# BMS_BQ76PL455.net
KiCad netlist of a schematic drawn in Altium Designer
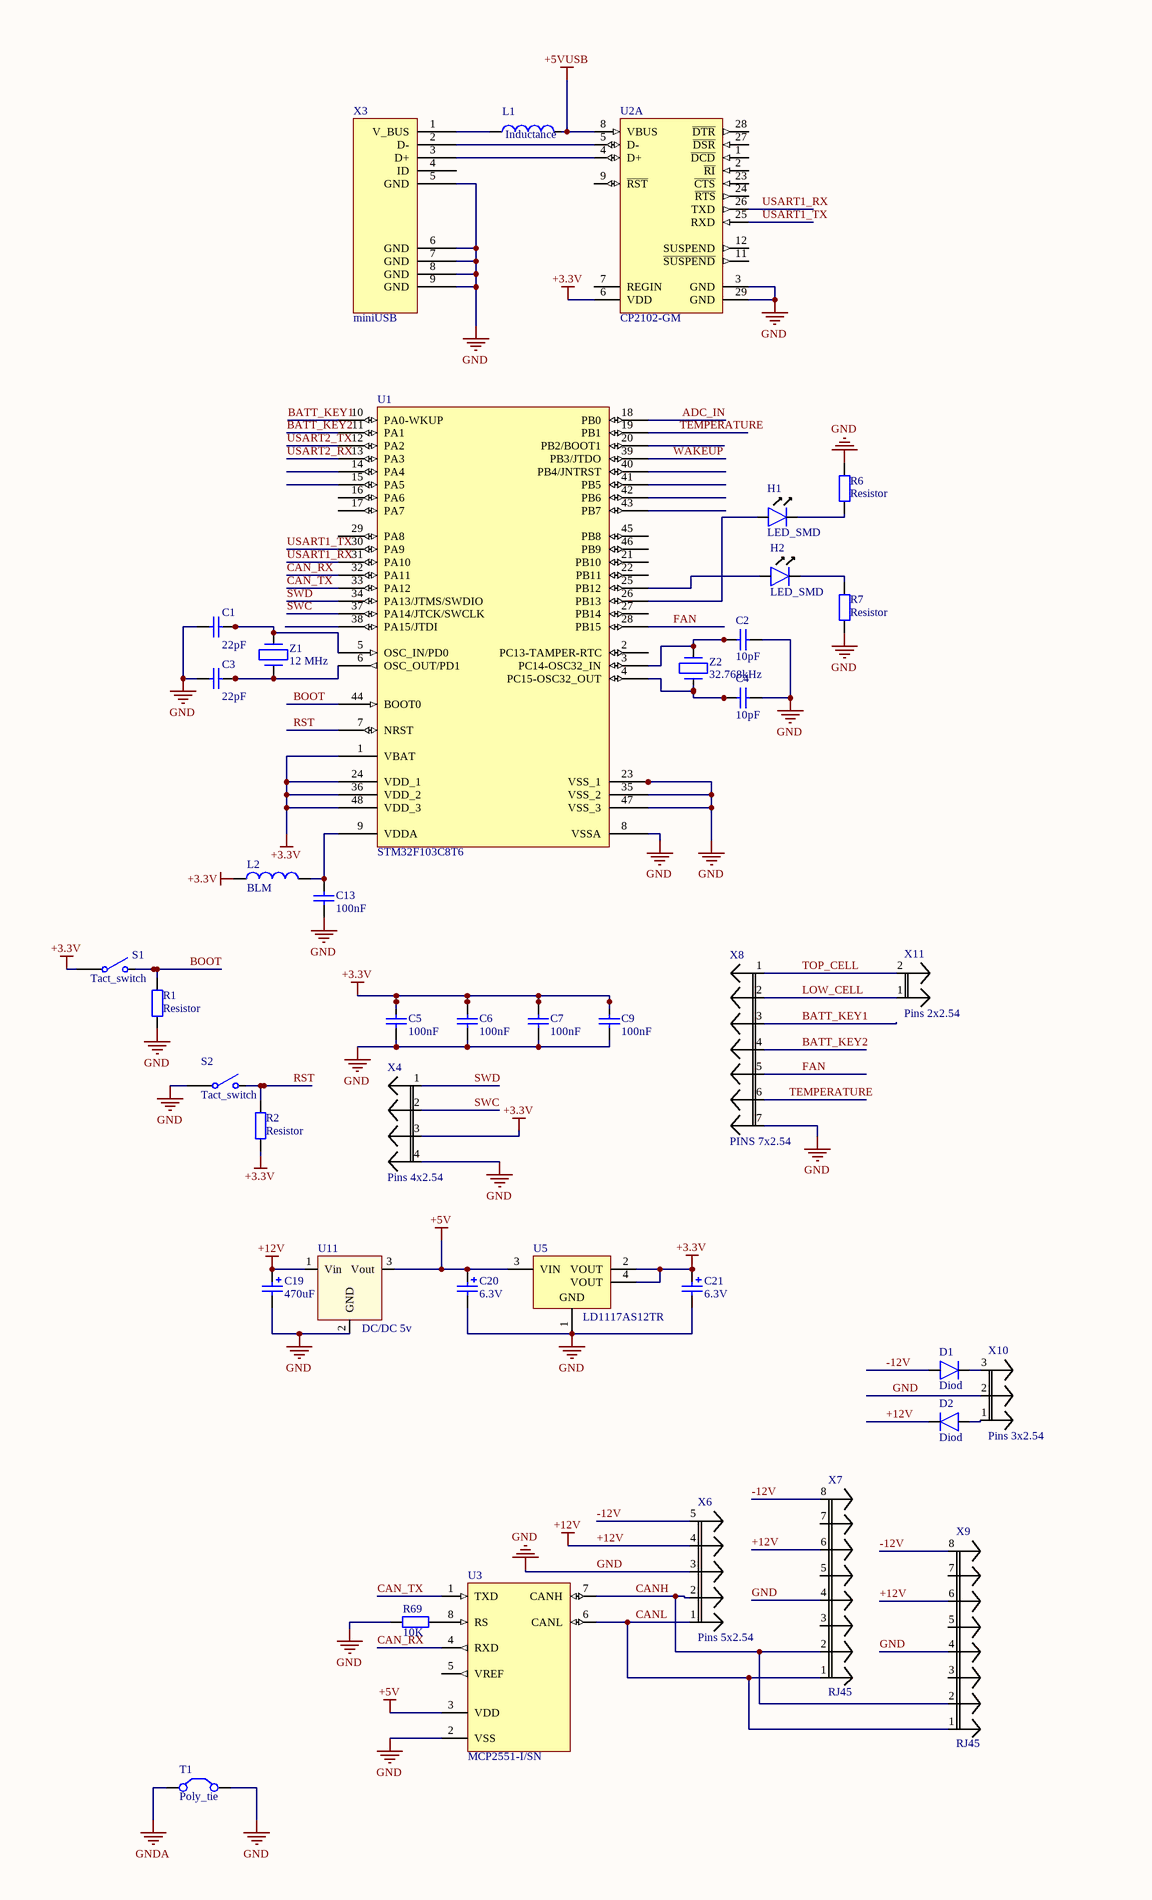
[diagram p0: BMS_BQ76PL455.SchDoc, left]
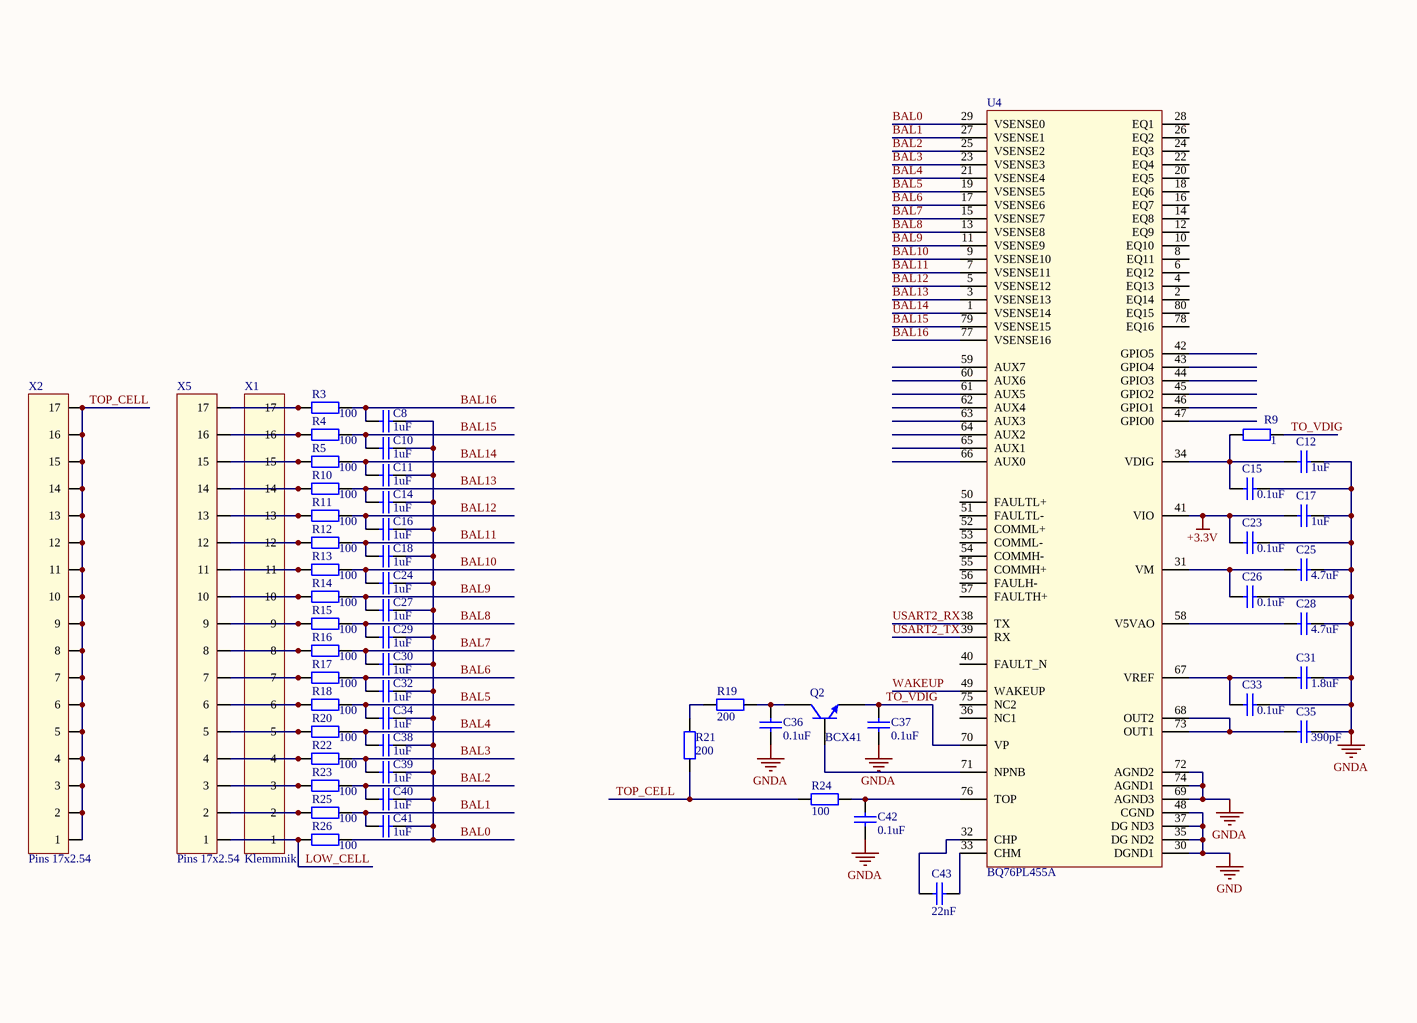
[diagram p1: BMS_BQ76PL455.SchDoc, right]

(export (version "E")
  (design (tool "Eeschema 10.0.6"))
  (components
    (comp (ref "C1") (value "22pF") (footprint "C0805") (libsource (lib "A_H_sch_lib") (part "Condensator")))
    (comp (ref "C2") (value "10pF") (footprint "C0805") (libsource (lib "A_H_sch_lib") (part "Condensator")))
    (comp (ref "C3") (value "22pF") (footprint "C0805") (libsource (lib "A_H_sch_lib") (part "Condensator")))
    (comp (ref "C4") (value "10pF") (footprint "C0805") (libsource (lib "A_H_sch_lib") (part "Condensator")))
    (comp (ref "C5") (value "100nF") (footprint "C0805") (libsource (lib "A_H_sch_lib") (part "Condensator")))
    (comp (ref "C6") (value "100nF") (footprint "C0805") (libsource (lib "A_H_sch_lib") (part "Condensator")))
    (comp (ref "C7") (value "100nF") (footprint "C0805") (libsource (lib "A_H_sch_lib") (part "Condensator")))
    (comp (ref "C8") (value "1uF") (footprint "C0805") (libsource (lib "A_H_sch_lib") (part "Condensator")))
    (comp (ref "C9") (value "100nF") (footprint "C0805") (libsource (lib "A_H_sch_lib") (part "Condensator")))
    (comp (ref "C10") (value "1uF") (footprint "C0805") (libsource (lib "A_H_sch_lib") (part "Condensator")))
    (comp (ref "C11") (value "1uF") (footprint "C0805") (libsource (lib "A_H_sch_lib") (part "Condensator")))
    (comp (ref "C12") (value "1uF") (footprint "C0805") (libsource (lib "A_H_sch_lib") (part "Condensator")))
    (comp (ref "C13")
      (value "100nF")
      (footprint "C0805")
      (libsource (lib "A_H_sch_lib") (part "Condensator"))
    )
    (comp (ref "C14") (value "1uF") (footprint "C0805") (libsource (lib "A_H_sch_lib") (part "Condensator")))
    (comp (ref "C15")
      (value "0.1uF")
      (footprint "C0805")
      (libsource (lib "A_H_sch_lib") (part "Condensator"))
    )
    (comp (ref "C16") (value "1uF") (footprint "C0805") (libsource (lib "A_H_sch_lib") (part "Condensator")))
    (comp (ref "C17") (value "1uF") (footprint "C0805") (libsource (lib "A_H_sch_lib") (part "Condensator")))
    (comp (ref "C18") (value "1uF") (footprint "C0805") (libsource (lib "A_H_sch_lib") (part "Condensator")))
    (comp (ref "C19")
      (value "470uF")
      (footprint "A_H_pcb_lib:Cap_El_SMD_10mm")
      (libsource (lib "A_H_sch_lib") (part "Cond_polar"))
    )
    (comp (ref "C20")
      (value "6.3V")
      (footprint "A_H_pcb_lib:CAP_EL_SMD_6.3mm")
      (libsource (lib "A_H_sch_lib") (part "Cond_polar"))
    )
    (comp (ref "C21")
      (value "6.3V")
      (footprint "A_H_pcb_lib:CAP_EL_SMD_6.3mm")
      (libsource (lib "A_H_sch_lib") (part "Cond_polar"))
    )
    (comp (ref "C23")
      (value "0.1uF")
      (footprint "C0805")
      (libsource (lib "A_H_sch_lib") (part "Condensator"))
    )
    (comp (ref "C24") (value "1uF") (footprint "C0805") (libsource (lib "A_H_sch_lib") (part "Condensator")))
    (comp (ref "C25")
      (value "4.7uF")
      (footprint "C0805")
      (libsource (lib "A_H_sch_lib") (part "Condensator"))
    )
    (comp (ref "C26")
      (value "0.1uF")
      (footprint "C0805")
      (libsource (lib "A_H_sch_lib") (part "Condensator"))
    )
    (comp (ref "C27") (value "1uF") (footprint "C0805") (libsource (lib "A_H_sch_lib") (part "Condensator")))
    (comp (ref "C28")
      (value "4.7uF")
      (footprint "C0805")
      (libsource (lib "A_H_sch_lib") (part "Condensator"))
    )
    (comp (ref "C29") (value "1uF") (footprint "C0805") (libsource (lib "A_H_sch_lib") (part "Condensator")))
    (comp (ref "C30") (value "1uF") (footprint "C0805") (libsource (lib "A_H_sch_lib") (part "Condensator")))
    (comp (ref "C31")
      (value "1.8uF")
      (footprint "C0805")
      (libsource (lib "A_H_sch_lib") (part "Condensator"))
    )
    (comp (ref "C32") (value "1uF") (footprint "C0805") (libsource (lib "A_H_sch_lib") (part "Condensator")))
    (comp (ref "C33")
      (value "0.1uF")
      (footprint "C0805")
      (libsource (lib "A_H_sch_lib") (part "Condensator"))
    )
    (comp (ref "C34") (value "1uF") (footprint "C0805") (libsource (lib "A_H_sch_lib") (part "Condensator")))
    (comp (ref "C35")
      (value "390pF")
      (footprint "C0805")
      (libsource (lib "A_H_sch_lib") (part "Condensator"))
    )
    (comp (ref "C36")
      (value "0.1uF")
      (footprint "C0805")
      (libsource (lib "A_H_sch_lib") (part "Condensator"))
    )
    (comp (ref "C37")
      (value "0.1uF")
      (footprint "C0805")
      (libsource (lib "A_H_sch_lib") (part "Condensator"))
    )
    (comp (ref "C38") (value "1uF") (footprint "C0805") (libsource (lib "A_H_sch_lib") (part "Condensator")))
    (comp (ref "C39") (value "1uF") (footprint "C0805") (libsource (lib "A_H_sch_lib") (part "Condensator")))
    (comp (ref "C40") (value "1uF") (footprint "C0805") (libsource (lib "A_H_sch_lib") (part "Condensator")))
    (comp (ref "C41") (value "1uF") (footprint "C0805") (libsource (lib "A_H_sch_lib") (part "Condensator")))
    (comp (ref "C42")
      (value "0.1uF")
      (footprint "C0805")
      (libsource (lib "A_H_sch_lib") (part "Condensator"))
    )
    (comp (ref "C43") (value "22nF") (footprint "C0805") (libsource (lib "A_H_sch_lib") (part "Condensator")))
    (comp (ref "D1")
      (value "Diod")
      (footprint "A_H_pcb_lib:SMB_DIODE")
      (libsource (lib "A_H_sch_lib") (part "Diod"))
    )
    (comp (ref "D2")
      (value "Diod")
      (footprint "A_H_pcb_lib:SMB_DIODE")
      (libsource (lib "A_H_sch_lib") (part "Diod"))
    )
    (comp (ref "H1") (value "LED_SMD") (footprint "C0805") (libsource (lib "A_H_sch_lib") (part "LED_SMD")))
    (comp (ref "H2") (value "LED_SMD") (footprint "C0805") (libsource (lib "A_H_sch_lib") (part "LED_SMD")))
    (comp (ref "L1")
      (value "Inductance")
      (footprint "L0805")
      (libsource (lib "A_H_sch_lib") (part "Inductance"))
    )
    (comp (ref "L2") (value "BLM") (footprint "L0805") (libsource (lib "A_H_sch_lib") (part "Inductance")))
    (comp (ref "Q2")
      (value "BCX41")
      (footprint "SOT-23A_N")
      (description "NPN General Purpose Amplifier")
      (fields (field (name "PUBLISHER") "Altium Limited"))
      (libsource (lib "FSC Discrete BJT") (part "BC817-25"))
    )
    (comp (ref "R1") (value "Resistor") (footprint "R0805") (libsource (lib "A_H_sch_lib") (part "Resistor")))
    (comp (ref "R2") (value "Resistor") (footprint "R0805") (libsource (lib "A_H_sch_lib") (part "Resistor")))
    (comp (ref "R3") (value "100") (footprint "R0805") (libsource (lib "") (part "Resistor_1")))
    (comp (ref "R4") (value "100") (footprint "R0805") (libsource (lib "") (part "Resistor_1")))
    (comp (ref "R5") (value "100") (footprint "R0805") (libsource (lib "") (part "Resistor_1")))
    (comp (ref "R6") (value "Resistor") (footprint "R0805") (libsource (lib "A_H_sch_lib") (part "Resistor")))
    (comp (ref "R7") (value "Resistor") (footprint "R0805") (libsource (lib "A_H_sch_lib") (part "Resistor")))
    (comp (ref "R9") (value "1") (footprint "R0805") (libsource (lib "") (part "Resistor_1")))
    (comp (ref "R10") (value "100") (footprint "R0805") (libsource (lib "") (part "Resistor_1")))
    (comp (ref "R11") (value "100") (footprint "R0805") (libsource (lib "") (part "Resistor_1")))
    (comp (ref "R12") (value "100") (footprint "R0805") (libsource (lib "") (part "Resistor_1")))
    (comp (ref "R13") (value "100") (footprint "R0805") (libsource (lib "") (part "Resistor_1")))
    (comp (ref "R14") (value "100") (footprint "R0805") (libsource (lib "") (part "Resistor_1")))
    (comp (ref "R15") (value "100") (footprint "R0805") (libsource (lib "") (part "Resistor_1")))
    (comp (ref "R16") (value "100") (footprint "R0805") (libsource (lib "") (part "Resistor_1")))
    (comp (ref "R17") (value "100") (footprint "R0805") (libsource (lib "") (part "Resistor_1")))
    (comp (ref "R18") (value "100") (footprint "R0805") (libsource (lib "") (part "Resistor_1")))
    (comp (ref "R19") (value "200") (footprint "R0805") (libsource (lib "") (part "Resistor_1")))
    (comp (ref "R20") (value "100") (footprint "R0805") (libsource (lib "") (part "Resistor_1")))
    (comp (ref "R21") (value "200") (footprint "R0805") (libsource (lib "") (part "Resistor_2")))
    (comp (ref "R22") (value "100") (footprint "R0805") (libsource (lib "") (part "Resistor_1")))
    (comp (ref "R23") (value "100") (footprint "R0805") (libsource (lib "") (part "Resistor_1")))
    (comp (ref "R24") (value "100") (footprint "R0805") (libsource (lib "") (part "Resistor_1")))
    (comp (ref "R25") (value "100") (footprint "R0805") (libsource (lib "") (part "Resistor_1")))
    (comp (ref "R26") (value "100") (footprint "R0805") (libsource (lib "") (part "Resistor_1")))
    (comp (ref "R69") (value "10K") (footprint "R0805") (libsource (lib "") (part "Resistor_1")))
    (comp (ref "S1")
      (value "Tact_switch")
      (footprint "Tact_switch_smd")
      (libsource (lib "A_H_sch_lib") (part "Tact_switch"))
    )
    (comp (ref "S2")
      (value "Tact_switch")
      (footprint "Tact_switch_smd")
      (libsource (lib "A_H_sch_lib") (part "Tact_switch"))
    )
    (comp (ref "T1")
      (value "Poly_tie")
      (footprint "A_H_pcb_lib:POLY_TIE_1x2")
      (libsource (lib "A_H_sch_lib") (part "Poly_tie"))
    )
    (comp (ref "U1")
      (value "STM32F103C8T6")
      (footprint "LQFP48_N")
      (description "STM32 ARM-based 32-bit MCU with 64 Kbytes Flash, 48-pin LQFP, Industrial Temperature")
      (fields (field (name "PUBLISHER") "Altium Limited"))
      (libsource (lib "ST Microcontroller 32-Bit STM32") (part "STM32F103C8T6"))
    )
    (comp (ref "U2")
      (value "CP2102-GM")
      (footprint "SLAB-QFN-28-3125x3125TP_N")
      (description "Single-Chip USB to UART Bridge, 1024 Bytes EEPROM, -40 to 85 degC, 28-pin QFN, Tube")
      (fields (field (name "MANUFACTURER") "Silicon Labs"))
      (libsource (lib "Silicon Labs Interface") (part "CP2102-GM"))
    )
    (comp (ref "U3")
      (value "MCP2551-I/SN")
      (footprint "SOIC-SN8_N")
      (description "High-Speed CAN Transceiver, 8-Pin SOIC, Industrial Temperature")
      (fields (field (name "PUBLISHER") "Altium Limited"))
      (libsource (lib "Microchip Interface") (part "MCP2551-I/SN"))
    )
    (comp (ref "U4")
      (value "BQ76PL455A")
      (footprint "A_H_pcb_lib:TQFP80 50P1400X1400X120-80N")
      (description "16-Cell Industrial Integrated Battery Monitor with Passive Cell Balancing")
      (libsource (lib "A_H_sch_lib") (part "BQ76PL455A"))
    )
    (comp (ref "U5")
      (value "LD1117AS12TR")
      (footprint "SOT-223_N")
      (description "1A, Low Drop Positive Voltage Regulator, 1.2V, 4-Pin SOT-223, Tape and Reel")
      (libsource (lib "STMicroelectronics Power Management Linear Regulator") (part "LD1117AS12TR"))
    )
    (comp (ref "U11")
      (value "DC/DC 5v")
      (footprint "A_H_pcb_lib:DC/DC R-78E")
      (libsource (lib "A_H_sch_lib") (part "DC/DC R-78E"))
    )
    (comp (ref "X1")
      (value "Klemmnik")
      (footprint "A_H_pcb_lib:Klemm 17")
      (libsource (lib "A_H_sch_lib") (part "Klemm 17"))
    )
    (comp (ref "X2")
      (value "Pins 17x2.54")
      (footprint "A_H_pcb_lib:Pins 17x2 2.54")
      (libsource (lib "A_H_sch_lib") (part "Pins 17x2.54"))
    )
    (comp (ref "X3")
      (value "miniUSB")
      (footprint "A_H_pcb_lib:miniUSB")
      (libsource (lib "A_H_sch_lib") (part "miniUSB"))
    )
    (comp (ref "X4")
      (value "Pins 4x2.54")
      (footprint "Pins 4x2.54")
      (libsource (lib "A_H_sch_lib") (part "Pins 4x2.54"))
    )
    (comp (ref "X5")
      (value "Pins 17x2.54")
      (footprint "A_H_pcb_lib:Pins 17x2 2.54")
      (libsource (lib "A_H_sch_lib") (part "Pins 17x2.54"))
    )
    (comp (ref "X6")
      (value "Pins 5x2.54")
      (footprint "Pins 5x2.54")
      (libsource (lib "A_H_sch_lib") (part "Pins 5x2.54"))
    )
    (comp (ref "X7")
      (value "RJ45")
      (footprint "A_H_pcb_lib:RJ45")
      (libsource (lib "A_H_sch_lib") (part "RJ45"))
    )
    (comp (ref "X8")
      (value "PINS 7x2.54")
      (footprint "PINS 7X2.54")
      (libsource (lib "A_H_sch_lib") (part "PINS 7x2.54"))
    )
    (comp (ref "X9")
      (value "RJ45")
      (footprint "A_H_pcb_lib:RJ45")
      (libsource (lib "A_H_sch_lib") (part "RJ45"))
    )
    (comp (ref "X10")
      (value "Pins 3x2.54")
      (footprint "Pins 3x2.54")
      (libsource (lib "A_H_sch_lib") (part "Pins 3x2.54"))
    )
    (comp (ref "X11")
      (value "Pins 2x2.54")
      (footprint "Pins 2x2.54")
      (libsource (lib "A_H_sch_lib") (part "Pins 2x2.54"))
    )
    (comp (ref "Z1")
      (value "12 MHz")
      (footprint "kx 13 12MHz")
      (libsource (lib "A_H_sch_lib") (part "KX 13 Geyer"))
    )
    (comp (ref "Z2")
      (value "32.768kHz")
      (footprint "Geyer KX - 327S 32.768kHz")
      (libsource (lib "A_H_sch_lib") (part "Crystal Oscillator"))
    )
  )
  (nets
    (net (code "1") (name "+3.3V") (class "Default")
      (node (ref "C17") (pin "1") (pinfunction "1_1") (pintype "passive"))
      (node (ref "C21") (pin "1") (pinfunction "1_1") (pintype "passive"))
      (node (ref "C23") (pin "1") (pinfunction "1_1") (pintype "passive"))
      (node (ref "C5") (pin "2") (pinfunction "2_2") (pintype "passive"))
      (node (ref "C6") (pin "2") (pinfunction "2_2") (pintype "passive"))
      (node (ref "C7") (pin "2") (pinfunction "2_2") (pintype "passive"))
      (node (ref "C9") (pin "2") (pinfunction "2_2") (pintype "passive"))
      (node (ref "L2") (pin "1") (pinfunction "1_1") (pintype "passive"))
      (node (ref "R2") (pin "1") (pinfunction "1_1") (pintype "passive"))
      (node (ref "S1") (pin "1") (pinfunction "COMMON_1") (pintype "passive"))
      (node (ref "U1") (pin "1") (pinfunction "VBAT_1") (pintype "power_in"))
      (node (ref "U1") (pin "24") (pinfunction "VDD_1_24") (pintype "power_in"))
      (node (ref "U1") (pin "36") (pinfunction "VDD_2_36") (pintype "power_in"))
      (node (ref "U1") (pin "48") (pinfunction "VDD_3_48") (pintype "power_in"))
      (node (ref "U2") (pin "6") (pinfunction "VDD_6") (pintype "power_in"))
      (node (ref "U4") (pin "41") (pinfunction "VIO_41") (pintype "passive"))
      (node (ref "U5") (pin "2") (pinfunction "VOUT_2") (pintype "power_in"))
      (node (ref "U5") (pin "4") (pinfunction "VOUT_4") (pintype "power_in"))
      (node (ref "X4") (pin "3") (pinfunction "3_3") (pintype "passive"))
    )
    (net (code "2") (name "+5V") (class "Default")
      (node (ref "C20") (pin "1") (pinfunction "1_1") (pintype "passive"))
      (node (ref "U11") (pin "3") (pinfunction "Vout_3") (pintype "passive"))
      (node (ref "U3") (pin "3") (pinfunction "VDD_3") (pintype "power_in"))
      (node (ref "U5") (pin "3") (pinfunction "VIN_3") (pintype "power_in"))
    )
    (net (code "3") (name "+5VUSB") (class "Default")
      (node (ref "L1") (pin "2") (pinfunction "2_2") (pintype "passive"))
      (node (ref "U2") (pin "8") (pinfunction "VBUS_8") (pintype "input"))
    )
    (net (code "4") (name "+12V") (class "Default")
      (node (ref "C19") (pin "1") (pinfunction "1_1") (pintype "passive"))
      (node (ref "D2") (pin "2") (pinfunction "2_2") (pintype "passive"))
      (node (ref "U11") (pin "1") (pinfunction "Vin_1") (pintype "passive"))
      (node (ref "X6") (pin "4") (pinfunction "4_4") (pintype "passive"))
      (node (ref "X7") (pin "6") (pinfunction "6_6") (pintype "passive"))
      (node (ref "X9") (pin "6") (pinfunction "6_6") (pintype "passive"))
    )
    (net (code "5") (name "/-12V") (class "Default")
      (node (ref "D1") (pin "1") (pinfunction "1_1") (pintype "passive"))
      (node (ref "X6") (pin "5") (pinfunction "5_5") (pintype "passive"))
      (node (ref "X7") (pin "8") (pinfunction "8_8") (pintype "passive"))
      (node (ref "X9") (pin "8") (pinfunction "8_8") (pintype "passive"))
    )
    (net (code "6") (name "/ADC_IN") (class "Default")
      (node (ref "U1") (pin "18") (pinfunction "PB0_18") (pintype "bidirectional"))
    )
    (net (code "7") (name "/BAL0") (class "Default")
      (node (ref "C10") (pin "2") (pinfunction "2_2") (pintype "passive"))
      (node (ref "C11") (pin "2") (pinfunction "2_2") (pintype "passive"))
      (node (ref "C14") (pin "2") (pinfunction "2_2") (pintype "passive"))
      (node (ref "C16") (pin "2") (pinfunction "2_2") (pintype "passive"))
      (node (ref "C18") (pin "2") (pinfunction "2_2") (pintype "passive"))
      (node (ref "C24") (pin "2") (pinfunction "2_2") (pintype "passive"))
      (node (ref "C27") (pin "2") (pinfunction "2_2") (pintype "passive"))
      (node (ref "C29") (pin "2") (pinfunction "2_2") (pintype "passive"))
      (node (ref "C30") (pin "2") (pinfunction "2_2") (pintype "passive"))
      (node (ref "C32") (pin "2") (pinfunction "2_2") (pintype "passive"))
      (node (ref "C34") (pin "2") (pinfunction "2_2") (pintype "passive"))
      (node (ref "C38") (pin "2") (pinfunction "2_2") (pintype "passive"))
      (node (ref "C39") (pin "2") (pinfunction "2_2") (pintype "passive"))
      (node (ref "C40") (pin "2") (pinfunction "2_2") (pintype "passive"))
      (node (ref "C41") (pin "2") (pinfunction "2_2") (pintype "passive"))
      (node (ref "C8") (pin "2") (pinfunction "2_2") (pintype "passive"))
      (node (ref "R26") (pin "1") (pinfunction "1_1") (pintype "passive"))
      (node (ref "U4") (pin "29") (pinfunction "VSENSE0_29") (pintype "passive"))
    )
    (net (code "8") (name "/BAL1") (class "Default")
      (node (ref "C41") (pin "1") (pinfunction "1_1") (pintype "passive"))
      (node (ref "R25") (pin "1") (pinfunction "1_1") (pintype "passive"))
      (node (ref "U4") (pin "27") (pinfunction "VSENSE1_27") (pintype "passive"))
    )
    (net (code "9") (name "/BAL2") (class "Default")
      (node (ref "C40") (pin "1") (pinfunction "1_1") (pintype "passive"))
      (node (ref "R23") (pin "1") (pinfunction "1_1") (pintype "passive"))
      (node (ref "U4") (pin "25") (pinfunction "VSENSE2_25") (pintype "passive"))
    )
    (net (code "10") (name "/BAL3") (class "Default")
      (node (ref "C39") (pin "1") (pinfunction "1_1") (pintype "passive"))
      (node (ref "R22") (pin "1") (pinfunction "1_1") (pintype "passive"))
      (node (ref "U4") (pin "23") (pinfunction "VSENSE3_23") (pintype "passive"))
    )
    (net (code "11") (name "/BAL4") (class "Default")
      (node (ref "C38") (pin "1") (pinfunction "1_1") (pintype "passive"))
      (node (ref "R20") (pin "1") (pinfunction "1_1") (pintype "passive"))
      (node (ref "U4") (pin "21") (pinfunction "VSENSE4_21") (pintype "passive"))
    )
    (net (code "12") (name "/BAL5") (class "Default")
      (node (ref "C34") (pin "1") (pinfunction "1_1") (pintype "passive"))
      (node (ref "R18") (pin "1") (pinfunction "1_1") (pintype "passive"))
      (node (ref "U4") (pin "19") (pinfunction "VSENSE5_19") (pintype "passive"))
    )
    (net (code "13") (name "/BAL6") (class "Default")
      (node (ref "C32") (pin "1") (pinfunction "1_1") (pintype "passive"))
      (node (ref "R17") (pin "1") (pinfunction "1_1") (pintype "passive"))
      (node (ref "U4") (pin "17") (pinfunction "VSENSE6_17") (pintype "passive"))
    )
    (net (code "14") (name "/BAL7") (class "Default")
      (node (ref "C30") (pin "1") (pinfunction "1_1") (pintype "passive"))
      (node (ref "R16") (pin "1") (pinfunction "1_1") (pintype "passive"))
      (node (ref "U4") (pin "15") (pinfunction "VSENSE7_15") (pintype "passive"))
    )
    (net (code "15") (name "/BAL8") (class "Default")
      (node (ref "C29") (pin "1") (pinfunction "1_1") (pintype "passive"))
      (node (ref "R15") (pin "1") (pinfunction "1_1") (pintype "passive"))
      (node (ref "U4") (pin "13") (pinfunction "VSENSE8_13") (pintype "passive"))
    )
    (net (code "16") (name "/BAL9") (class "Default")
      (node (ref "C27") (pin "1") (pinfunction "1_1") (pintype "passive"))
      (node (ref "R14") (pin "1") (pinfunction "1_1") (pintype "passive"))
      (node (ref "U4") (pin "11") (pinfunction "VSENSE9_11") (pintype "passive"))
    )
    (net (code "17") (name "/BAL10") (class "Default")
      (node (ref "C24") (pin "1") (pinfunction "1_1") (pintype "passive"))
      (node (ref "R13") (pin "1") (pinfunction "1_1") (pintype "passive"))
      (node (ref "U4") (pin "9") (pinfunction "VSENSE10_9") (pintype "passive"))
    )
    (net (code "18") (name "/BAL11") (class "Default")
      (node (ref "C18") (pin "1") (pinfunction "1_1") (pintype "passive"))
      (node (ref "R12") (pin "1") (pinfunction "1_1") (pintype "passive"))
      (node (ref "U4") (pin "7") (pinfunction "VSENSE11_7") (pintype "passive"))
    )
    (net (code "19") (name "/BAL12") (class "Default")
      (node (ref "C16") (pin "1") (pinfunction "1_1") (pintype "passive"))
      (node (ref "R11") (pin "1") (pinfunction "1_1") (pintype "passive"))
      (node (ref "U4") (pin "5") (pinfunction "VSENSE12_5") (pintype "passive"))
    )
    (net (code "20") (name "/BAL13") (class "Default")
      (node (ref "C14") (pin "1") (pinfunction "1_1") (pintype "passive"))
      (node (ref "R10") (pin "1") (pinfunction "1_1") (pintype "passive"))
      (node (ref "U4") (pin "3") (pinfunction "VSENSE13_3") (pintype "passive"))
    )
    (net (code "21") (name "/BAL14") (class "Default")
      (node (ref "C11") (pin "1") (pinfunction "1_1") (pintype "passive"))
      (node (ref "R5") (pin "1") (pinfunction "1_1") (pintype "passive"))
      (node (ref "U4") (pin "1") (pinfunction "VSENSE14_1") (pintype "passive"))
    )
    (net (code "22") (name "/BAL15") (class "Default")
      (node (ref "C10") (pin "1") (pinfunction "1_1") (pintype "passive"))
      (node (ref "R4") (pin "1") (pinfunction "1_1") (pintype "passive"))
      (node (ref "U4") (pin "79") (pinfunction "VSENSE15_79") (pintype "passive"))
    )
    (net (code "23") (name "/BAL16") (class "Default")
      (node (ref "C8") (pin "1") (pinfunction "1_1") (pintype "passive"))
      (node (ref "R3") (pin "1") (pinfunction "1_1") (pintype "passive"))
      (node (ref "U4") (pin "77") (pinfunction "VSENSE16_77") (pintype "passive"))
    )
    (net (code "24") (name "/BATT_KEY1") (class "Default")
      (node (ref "U1") (pin "10") (pinfunction "PA0-WKUP_10") (pintype "bidirectional"))
      (node (ref "X8") (pin "3") (pinfunction "3_3") (pintype "passive"))
    )
    (net (code "25") (name "/BATT_KEY2") (class "Default")
      (node (ref "U1") (pin "11") (pinfunction "PA1_11") (pintype "bidirectional"))
      (node (ref "X8") (pin "4") (pinfunction "4_4") (pintype "passive"))
    )
    (net (code "26") (name "/BOOT") (class "Default")
      (node (ref "R1") (pin "2") (pinfunction "2_2") (pintype "passive"))
      (node (ref "S1") (pin "2") (pinfunction "NO_2") (pintype "passive"))
      (node (ref "U1") (pin "44") (pinfunction "BOOT0_44") (pintype "input"))
    )
    (net (code "27") (name "/CANH") (class "Default")
      (node (ref "U3") (pin "7") (pinfunction "CANH_7") (pintype "bidirectional"))
      (node (ref "X6") (pin "2") (pinfunction "2_2") (pintype "passive"))
      (node (ref "X7") (pin "2") (pinfunction "2_2") (pintype "passive"))
      (node (ref "X9") (pin "2") (pinfunction "2_2") (pintype "passive"))
    )
    (net (code "28") (name "/CANL") (class "Default")
      (node (ref "U3") (pin "6") (pinfunction "CANL_6") (pintype "bidirectional"))
      (node (ref "X6") (pin "1") (pinfunction "1_1") (pintype "passive"))
      (node (ref "X7") (pin "1") (pinfunction "1_1") (pintype "passive"))
      (node (ref "X9") (pin "1") (pinfunction "1_1") (pintype "passive"))
    )
    (net (code "29") (name "/CAN_RX") (class "Default")
      (node (ref "U1") (pin "32") (pinfunction "PA11_32") (pintype "bidirectional"))
      (node (ref "U3") (pin "4") (pinfunction "RXD_4") (pintype "output"))
    )
    (net (code "30") (name "/CAN_TX") (class "Default")
      (node (ref "U1") (pin "33") (pinfunction "PA12_33") (pintype "bidirectional"))
      (node (ref "U3") (pin "1") (pinfunction "TXD_1") (pintype "input"))
    )
    (net (code "31") (name "/FAN") (class "Default")
      (node (ref "U1") (pin "28") (pinfunction "PB15_28") (pintype "bidirectional"))
      (node (ref "X8") (pin "5") (pinfunction "5_5") (pintype "passive"))
    )
    (net (code "32") (name "/LOW_CELL") (class "Default")
      (node (ref "R26") (pin "2") (pinfunction "2_2") (pintype "passive"))
      (node (ref "X1") (pin "1") (pinfunction "1_1") (pintype "passive"))
      (node (ref "X11") (pin "1") (pinfunction "1_1") (pintype "passive"))
      (node (ref "X5") (pin "1") (pinfunction "1_1") (pintype "passive"))
      (node (ref "X8") (pin "2") (pinfunction "2_2") (pintype "passive"))
    )
    (net (code "33") (name "/RST") (class "Default")
      (node (ref "R2") (pin "2") (pinfunction "2_2") (pintype "passive"))
      (node (ref "S2") (pin "2") (pinfunction "NO_2") (pintype "passive"))
      (node (ref "U1") (pin "7") (pinfunction "NRST_7") (pintype "bidirectional"))
    )
    (net (code "34") (name "/SWC") (class "Default")
      (node (ref "U1") (pin "37") (pinfunction "PA14/JTCK/SWCLK_37") (pintype "bidirectional"))
      (node (ref "X4") (pin "2") (pinfunction "2_2") (pintype "passive"))
    )
    (net (code "35") (name "/SWD") (class "Default")
      (node (ref "U1") (pin "34") (pinfunction "PA13/JTMS/SWDIO_34") (pintype "bidirectional"))
      (node (ref "X4") (pin "1") (pinfunction "1_1") (pintype "passive"))
    )
    (net (code "36") (name "/TEMPERATURE") (class "Default")
      (node (ref "U1") (pin "19") (pinfunction "PB1_19") (pintype "bidirectional"))
      (node (ref "X8") (pin "6") (pinfunction "6_6") (pintype "passive"))
    )
    (net (code "37") (name "/TOP_CELL") (class "Default")
      (node (ref "R21") (pin "2") (pinfunction "2_2") (pintype "passive"))
      (node (ref "R24") (pin "2") (pinfunction "2_2") (pintype "passive"))
      (node (ref "X11") (pin "2") (pinfunction "2_2") (pintype "passive"))
      (node (ref "X2") (pin "1") (pinfunction "1_1") (pintype "passive"))
      (node (ref "X2") (pin "10") (pinfunction "10_10") (pintype "passive"))
      (node (ref "X2") (pin "11") (pinfunction "11_11") (pintype "passive"))
      (node (ref "X2") (pin "12") (pinfunction "12_12") (pintype "passive"))
      (node (ref "X2") (pin "13") (pinfunction "13_13") (pintype "passive"))
      (node (ref "X2") (pin "14") (pinfunction "14_14") (pintype "passive"))
      (node (ref "X2") (pin "15") (pinfunction "15_15") (pintype "passive"))
      (node (ref "X2") (pin "16") (pinfunction "16_16") (pintype "passive"))
      (node (ref "X2") (pin "17") (pinfunction "17_17") (pintype "passive"))
      (node (ref "X2") (pin "2") (pinfunction "2_2") (pintype "passive"))
      (node (ref "X2") (pin "3") (pinfunction "3_3") (pintype "passive"))
      (node (ref "X2") (pin "4") (pinfunction "4_4") (pintype "passive"))
      (node (ref "X2") (pin "5") (pinfunction "5_5") (pintype "passive"))
      (node (ref "X2") (pin "6") (pinfunction "6_6") (pintype "passive"))
      (node (ref "X2") (pin "7") (pinfunction "7_7") (pintype "passive"))
      (node (ref "X2") (pin "8") (pinfunction "8_8") (pintype "passive"))
      (node (ref "X2") (pin "9") (pinfunction "9_9") (pintype "passive"))
      (node (ref "X8") (pin "1") (pinfunction "1_1") (pintype "passive"))
    )
    (net (code "38") (name "/TO_VDIG") (class "Default")
      (node (ref "C37") (pin "2") (pinfunction "2_2") (pintype "passive"))
      (node (ref "Q2") (pin "2") (pinfunction "E_2") (pintype "passive"))
      (node (ref "R9") (pin "1") (pinfunction "1_1") (pintype "passive"))
      (node (ref "U4") (pin "70") (pinfunction "VP_70") (pintype "passive"))
    )
    (net (code "39") (name "/USART1_RX") (class "Default")
      (node (ref "U1") (pin "31") (pinfunction "PA10_31") (pintype "bidirectional"))
      (node (ref "U2") (pin "26") (pinfunction "TXD_26") (pintype "output"))
    )
    (net (code "40") (name "/USART1_TX") (class "Default")
      (node (ref "U1") (pin "30") (pinfunction "PA9_30") (pintype "bidirectional"))
      (node (ref "U2") (pin "25") (pinfunction "RXD_25") (pintype "input"))
    )
    (net (code "41") (name "/USART2_RX") (class "Default")
      (node (ref "U1") (pin "13") (pinfunction "PA3_13") (pintype "bidirectional"))
      (node (ref "U4") (pin "38") (pinfunction "TX_38") (pintype "passive"))
    )
    (net (code "42") (name "/USART2_TX") (class "Default")
      (node (ref "U1") (pin "12") (pinfunction "PA2_12") (pintype "bidirectional"))
      (node (ref "U4") (pin "39") (pinfunction "RX_39") (pintype "passive"))
    )
    (net (code "43") (name "/WAKEUP") (class "Default")
      (node (ref "U1") (pin "39") (pinfunction "PB3/JTDO_39") (pintype "bidirectional"))
      (node (ref "U4") (pin "49") (pinfunction "WAKEUP_49") (pintype "passive"))
    )
    (net (code "44") (name "GND") (class "Default")
      (node (ref "C1") (pin "1") (pinfunction "1_1") (pintype "passive"))
      (node (ref "C13") (pin "1") (pinfunction "1_1") (pintype "passive"))
      (node (ref "C19") (pin "2") (pinfunction "2_2") (pintype "passive"))
      (node (ref "C2") (pin "1") (pinfunction "1_1") (pintype "passive"))
      (node (ref "C20") (pin "2") (pinfunction "2_2") (pintype "passive"))
      (node (ref "C21") (pin "2") (pinfunction "2_2") (pintype "passive"))
      (node (ref "C3") (pin "1") (pinfunction "1_1") (pintype "passive"))
      (node (ref "C4") (pin "1") (pinfunction "1_1") (pintype "passive"))
      (node (ref "C5") (pin "1") (pinfunction "1_1") (pintype "passive"))
      (node (ref "C6") (pin "1") (pinfunction "1_1") (pintype "passive"))
      (node (ref "C7") (pin "1") (pinfunction "1_1") (pintype "passive"))
      (node (ref "C9") (pin "1") (pinfunction "1_1") (pintype "passive"))
      (node (ref "R1") (pin "1") (pinfunction "1_1") (pintype "passive"))
      (node (ref "R6") (pin "2") (pinfunction "2_2") (pintype "passive"))
      (node (ref "R69") (pin "2") (pinfunction "2_2") (pintype "passive"))
      (node (ref "R7") (pin "1") (pinfunction "1_1") (pintype "passive"))
      (node (ref "S2") (pin "1") (pinfunction "COMMON_1") (pintype "passive"))
      (node (ref "T1") (pin "2") (pinfunction "C2_2") (pintype "passive"))
      (node (ref "U1") (pin "23") (pinfunction "VSS_1_23") (pintype "power_in"))
      (node (ref "U1") (pin "35") (pinfunction "VSS_2_35") (pintype "power_in"))
      (node (ref "U1") (pin "47") (pinfunction "VSS_3_47") (pintype "power_in"))
      (node (ref "U1") (pin "8") (pinfunction "VSSA_8") (pintype "power_in"))
      (node (ref "U11") (pin "2") (pinfunction "GND_2") (pintype "passive"))
      (node (ref "U2") (pin "29") (pinfunction "GND_29") (pintype "power_in"))
      (node (ref "U2") (pin "3") (pinfunction "GND_3") (pintype "power_in"))
      (node (ref "U3") (pin "2") (pinfunction "VSS_2") (pintype "power_in"))
      (node (ref "U4") (pin "30") (pinfunction "DGND1_30") (pintype "passive"))
      (node (ref "U4") (pin "35") (pinfunction "DG_ND2_35") (pintype "passive"))
      (node (ref "U4") (pin "37") (pinfunction "DG_ND3_37") (pintype "passive"))
      (node (ref "U4") (pin "48") (pinfunction "CGND_48") (pintype "passive"))
      (node (ref "U5") (pin "1") (pinfunction "GND_1") (pintype "power_in"))
      (node (ref "X10") (pin "2") (pinfunction "2_2") (pintype "passive"))
      (node (ref "X3") (pin "5") (pinfunction "GND_5") (pintype "passive"))
      (node (ref "X3") (pin "6") (pinfunction "GND_6") (pintype "passive"))
      (node (ref "X3") (pin "7") (pinfunction "GND_7") (pintype "passive"))
      (node (ref "X3") (pin "8") (pinfunction "GND_8") (pintype "passive"))
      (node (ref "X3") (pin "9") (pinfunction "GND_9") (pintype "passive"))
      (node (ref "X4") (pin "4") (pinfunction "4_4") (pintype "passive"))
      (node (ref "X6") (pin "3") (pinfunction "3_3") (pintype "passive"))
      (node (ref "X7") (pin "4") (pinfunction "4_4") (pintype "passive"))
      (node (ref "X8") (pin "7") (pinfunction "7_7") (pintype "passive"))
      (node (ref "X9") (pin "4") (pinfunction "4_4") (pintype "passive"))
    )
    (net (code "45") (name "GNDA") (class "Default")
      (node (ref "C12") (pin "2") (pinfunction "2_2") (pintype "passive"))
      (node (ref "C15") (pin "2") (pinfunction "2_2") (pintype "passive"))
      (node (ref "C17") (pin "2") (pinfunction "2_2") (pintype "passive"))
      (node (ref "C23") (pin "2") (pinfunction "2_2") (pintype "passive"))
      (node (ref "C25") (pin "2") (pinfunction "2_2") (pintype "passive"))
      (node (ref "C26") (pin "2") (pinfunction "2_2") (pintype "passive"))
      (node (ref "C28") (pin "2") (pinfunction "2_2") (pintype "passive"))
      (node (ref "C31") (pin "2") (pinfunction "2_2") (pintype "passive"))
      (node (ref "C33") (pin "2") (pinfunction "2_2") (pintype "passive"))
      (node (ref "C35") (pin "2") (pinfunction "2_2") (pintype "passive"))
      (node (ref "C36") (pin "1") (pinfunction "1_1") (pintype "passive"))
      (node (ref "C37") (pin "1") (pinfunction "1_1") (pintype "passive"))
      (node (ref "C42") (pin "1") (pinfunction "1_1") (pintype "passive"))
      (node (ref "T1") (pin "1") (pinfunction "C1_1") (pintype "passive"))
      (node (ref "U4") (pin "69") (pinfunction "AGND3_69") (pintype "passive"))
      (node (ref "U4") (pin "72") (pinfunction "AGND2_72") (pintype "passive"))
      (node (ref "U4") (pin "74") (pinfunction "AGND1_74") (pintype "passive"))
    )
    (net (code "46") (name "Net-(D1-Pad2)") (class "Default")
      (node (ref "D1") (pin "2") (pinfunction "2_2") (pintype "passive"))
      (node (ref "X10") (pin "3") (pinfunction "3_3") (pintype "passive"))
    )
    (net (code "47") (name "Net-(D2-Pad1)") (class "Default")
      (node (ref "D2") (pin "1") (pinfunction "1_1") (pintype "passive"))
      (node (ref "X10") (pin "1") (pinfunction "1_1") (pintype "passive"))
    )
    (net (code "48") (name "Net-(H1-Pad2)") (class "Default")
      (node (ref "H1") (pin "2") (pinfunction "2_2") (pintype "passive"))
      (node (ref "R6") (pin "1") (pinfunction "1_1") (pintype "passive"))
    )
    (net (code "49") (name "Net-(H2-Pad2)") (class "Default")
      (node (ref "H2") (pin "2") (pinfunction "2_2") (pintype "passive"))
      (node (ref "R7") (pin "2") (pinfunction "2_2") (pintype "passive"))
    )
    (net (code "50") (name "Net-(Q2-B)") (class "Default")
      (node (ref "Q2") (pin "1") (pinfunction "B_1") (pintype "passive"))
      (node (ref "U4") (pin "71") (pinfunction "NPNB_71") (pintype "passive"))
    )
    (net (code "51") (name "Net-(Q2-C)") (class "Default")
      (node (ref "C36") (pin "2") (pinfunction "2_2") (pintype "passive"))
      (node (ref "Q2") (pin "3") (pinfunction "C_3") (pintype "passive"))
      (node (ref "R19") (pin "1") (pinfunction "1_1") (pintype "passive"))
    )
    (net (code "52") (name "Net-(R3-Pad2)") (class "Default")
      (node (ref "R3") (pin "2") (pinfunction "2_2") (pintype "passive"))
      (node (ref "X1") (pin "17") (pinfunction "17_17") (pintype "passive"))
      (node (ref "X5") (pin "17") (pinfunction "17_17") (pintype "passive"))
    )
    (net (code "53") (name "Net-(R4-Pad2)") (class "Default")
      (node (ref "R4") (pin "2") (pinfunction "2_2") (pintype "passive"))
      (node (ref "X1") (pin "16") (pinfunction "16_16") (pintype "passive"))
      (node (ref "X5") (pin "16") (pinfunction "16_16") (pintype "passive"))
    )
    (net (code "54") (name "Net-(R5-Pad2)") (class "Default")
      (node (ref "R5") (pin "2") (pinfunction "2_2") (pintype "passive"))
      (node (ref "X1") (pin "15") (pinfunction "15_15") (pintype "passive"))
      (node (ref "X5") (pin "15") (pinfunction "15_15") (pintype "passive"))
    )
    (net (code "55") (name "Net-(R10-Pad2)") (class "Default")
      (node (ref "R10") (pin "2") (pinfunction "2_2") (pintype "passive"))
      (node (ref "X1") (pin "14") (pinfunction "14_14") (pintype "passive"))
      (node (ref "X5") (pin "14") (pinfunction "14_14") (pintype "passive"))
    )
    (net (code "56") (name "Net-(R11-Pad2)") (class "Default")
      (node (ref "R11") (pin "2") (pinfunction "2_2") (pintype "passive"))
      (node (ref "X1") (pin "13") (pinfunction "13_13") (pintype "passive"))
      (node (ref "X5") (pin "13") (pinfunction "13_13") (pintype "passive"))
    )
    (net (code "57") (name "Net-(R12-Pad2)") (class "Default")
      (node (ref "R12") (pin "2") (pinfunction "2_2") (pintype "passive"))
      (node (ref "X1") (pin "12") (pinfunction "12_12") (pintype "passive"))
      (node (ref "X5") (pin "12") (pinfunction "12_12") (pintype "passive"))
    )
    (net (code "58") (name "Net-(R13-Pad2)") (class "Default")
      (node (ref "R13") (pin "2") (pinfunction "2_2") (pintype "passive"))
      (node (ref "X1") (pin "11") (pinfunction "11_11") (pintype "passive"))
      (node (ref "X5") (pin "11") (pinfunction "11_11") (pintype "passive"))
    )
    (net (code "59") (name "Net-(R14-Pad2)") (class "Default")
      (node (ref "R14") (pin "2") (pinfunction "2_2") (pintype "passive"))
      (node (ref "X1") (pin "10") (pinfunction "10_10") (pintype "passive"))
      (node (ref "X5") (pin "10") (pinfunction "10_10") (pintype "passive"))
    )
    (net (code "60") (name "Net-(R15-Pad2)") (class "Default")
      (node (ref "R15") (pin "2") (pinfunction "2_2") (pintype "passive"))
      (node (ref "X1") (pin "9") (pinfunction "9_9") (pintype "passive"))
      (node (ref "X5") (pin "9") (pinfunction "9_9") (pintype "passive"))
    )
    (net (code "61") (name "Net-(R16-Pad2)") (class "Default")
      (node (ref "R16") (pin "2") (pinfunction "2_2") (pintype "passive"))
      (node (ref "X1") (pin "8") (pinfunction "8_8") (pintype "passive"))
      (node (ref "X5") (pin "8") (pinfunction "8_8") (pintype "passive"))
    )
    (net (code "62") (name "Net-(R17-Pad2)") (class "Default")
      (node (ref "R17") (pin "2") (pinfunction "2_2") (pintype "passive"))
      (node (ref "X1") (pin "7") (pinfunction "7_7") (pintype "passive"))
      (node (ref "X5") (pin "7") (pinfunction "7_7") (pintype "passive"))
    )
    (net (code "63") (name "Net-(R18-Pad2)") (class "Default")
      (node (ref "R18") (pin "2") (pinfunction "2_2") (pintype "passive"))
      (node (ref "X1") (pin "6") (pinfunction "6_6") (pintype "passive"))
      (node (ref "X5") (pin "6") (pinfunction "6_6") (pintype "passive"))
    )
    (net (code "64") (name "Net-(R19-Pad2)") (class "Default")
      (node (ref "R19") (pin "2") (pinfunction "2_2") (pintype "passive"))
      (node (ref "R21") (pin "1") (pinfunction "1_1") (pintype "passive"))
    )
    (net (code "65") (name "Net-(R20-Pad2)") (class "Default")
      (node (ref "R20") (pin "2") (pinfunction "2_2") (pintype "passive"))
      (node (ref "X1") (pin "5") (pinfunction "5_5") (pintype "passive"))
      (node (ref "X5") (pin "5") (pinfunction "5_5") (pintype "passive"))
    )
    (net (code "66") (name "Net-(R22-Pad2)") (class "Default")
      (node (ref "R22") (pin "2") (pinfunction "2_2") (pintype "passive"))
      (node (ref "X1") (pin "4") (pinfunction "4_4") (pintype "passive"))
      (node (ref "X5") (pin "4") (pinfunction "4_4") (pintype "passive"))
    )
    (net (code "67") (name "Net-(R23-Pad2)") (class "Default")
      (node (ref "R23") (pin "2") (pinfunction "2_2") (pintype "passive"))
      (node (ref "X1") (pin "3") (pinfunction "3_3") (pintype "passive"))
      (node (ref "X5") (pin "3") (pinfunction "3_3") (pintype "passive"))
    )
    (net (code "68") (name "Net-(R25-Pad2)") (class "Default")
      (node (ref "R25") (pin "2") (pinfunction "2_2") (pintype "passive"))
      (node (ref "X1") (pin "2") (pinfunction "2_2") (pintype "passive"))
      (node (ref "X5") (pin "2") (pinfunction "2_2") (pintype "passive"))
    )
    (net (code "69") (name "Net-(U1-OSC_IN{slash}PD0)") (class "Default")
      (node (ref "C1") (pin "2") (pinfunction "2_2") (pintype "passive"))
      (node (ref "U1") (pin "5") (pinfunction "OSC_IN/PD0_5") (pintype "input"))
      (node (ref "Z1") (pin "1") (pinfunction "1_1") (pintype "passive"))
    )
    (net (code "70") (name "Net-(U1-OSC_OUT{slash}PD1)") (class "Default")
      (node (ref "C3") (pin "2") (pinfunction "2_2") (pintype "passive"))
      (node (ref "U1") (pin "6") (pinfunction "OSC_OUT/PD1_6") (pintype "output"))
      (node (ref "Z1") (pin "3") (pinfunction "3_3") (pintype "passive"))
    )
    (net (code "71") (name "Net-(U1-PB12)") (class "Default")
      (node (ref "H2") (pin "1") (pinfunction "1_1") (pintype "passive"))
      (node (ref "U1") (pin "25") (pinfunction "PB12_25") (pintype "bidirectional"))
    )
    (net (code "72") (name "Net-(U1-PB13)") (class "Default")
      (node (ref "H1") (pin "1") (pinfunction "1_1") (pintype "passive"))
      (node (ref "U1") (pin "26") (pinfunction "PB13_26") (pintype "bidirectional"))
    )
    (net (code "73") (name "Net-(U1-PC14-OSC32_IN)") (class "Default")
      (node (ref "C2") (pin "2") (pinfunction "2_2") (pintype "passive"))
      (node (ref "U1") (pin "3") (pinfunction "PC14-OSC32_IN_3") (pintype "bidirectional"))
      (node (ref "Z2") (pin "1") (pinfunction "1_1") (pintype "passive"))
    )
    (net (code "74") (name "Net-(U1-PC15-OSC32_OUT)") (class "Default")
      (node (ref "C4") (pin "2") (pinfunction "2_2") (pintype "passive"))
      (node (ref "U1") (pin "4") (pinfunction "PC15-OSC32_OUT_4") (pintype "bidirectional"))
      (node (ref "Z2") (pin "2") (pinfunction "2_2") (pintype "passive"))
    )
    (net (code "75") (name "Net-(U1-VDDA)") (class "Default")
      (node (ref "C13") (pin "2") (pinfunction "2_2") (pintype "passive"))
      (node (ref "L2") (pin "2") (pinfunction "2_2") (pintype "passive"))
      (node (ref "U1") (pin "9") (pinfunction "VDDA_9") (pintype "power_in"))
    )
    (net (code "76") (name "Net-(U2A-D+)") (class "Default")
      (node (ref "U2") (pin "4") (pinfunction "D+_4") (pintype "bidirectional"))
      (node (ref "X3") (pin "3") (pinfunction "D+_3") (pintype "passive"))
    )
    (net (code "77") (name "Net-(U2A-D-)") (class "Default")
      (node (ref "U2") (pin "5") (pinfunction "D-_5") (pintype "bidirectional"))
      (node (ref "X3") (pin "2") (pinfunction "D-_2") (pintype "passive"))
    )
    (net (code "78") (name "Net-(U3-RS)") (class "Default")
      (node (ref "R69") (pin "1") (pinfunction "1_1") (pintype "passive"))
      (node (ref "U3") (pin "8") (pinfunction "RS_8") (pintype "input"))
    )
    (net (code "79") (name "Net-(U4-CHM)") (class "Default")
      (node (ref "C43") (pin "2") (pinfunction "2_2") (pintype "passive"))
      (node (ref "U4") (pin "33") (pinfunction "CHM_33") (pintype "passive"))
    )
    (net (code "80") (name "Net-(U4-CHP)") (class "Default")
      (node (ref "C43") (pin "1") (pinfunction "1_1") (pintype "passive"))
      (node (ref "U4") (pin "32") (pinfunction "CHP_32") (pintype "passive"))
    )
    (net (code "81") (name "Net-(U4-OUT1)") (class "Default")
      (node (ref "C35") (pin "1") (pinfunction "1_1") (pintype "passive"))
      (node (ref "U4") (pin "68") (pinfunction "OUT2_68") (pintype "passive"))
      (node (ref "U4") (pin "73") (pinfunction "OUT1_73") (pintype "passive"))
    )
    (net (code "82") (name "Net-(U4-TOP)") (class "Default")
      (node (ref "C42") (pin "2") (pinfunction "2_2") (pintype "passive"))
      (node (ref "R24") (pin "1") (pinfunction "1_1") (pintype "passive"))
      (node (ref "U4") (pin "76") (pinfunction "TOP_76") (pintype "passive"))
    )
    (net (code "83") (name "Net-(U4-V5VAO)") (class "Default")
      (node (ref "C28") (pin "1") (pinfunction "1_1") (pintype "passive"))
      (node (ref "U4") (pin "58") (pinfunction "V5VAO_58") (pintype "passive"))
    )
    (net (code "84") (name "Net-(U4-VDIG)") (class "Default")
      (node (ref "C12") (pin "1") (pinfunction "1_1") (pintype "passive"))
      (node (ref "C15") (pin "1") (pinfunction "1_1") (pintype "passive"))
      (node (ref "R9") (pin "2") (pinfunction "2_2") (pintype "passive"))
      (node (ref "U4") (pin "34") (pinfunction "VDIG_34") (pintype "passive"))
    )
    (net (code "85") (name "Net-(U4-VM)") (class "Default")
      (node (ref "C25") (pin "1") (pinfunction "1_1") (pintype "passive"))
      (node (ref "C26") (pin "1") (pinfunction "1_1") (pintype "passive"))
      (node (ref "U4") (pin "31") (pinfunction "VM_31") (pintype "passive"))
    )
    (net (code "86") (name "Net-(U4-VREF)") (class "Default")
      (node (ref "C31") (pin "1") (pinfunction "1_1") (pintype "passive"))
      (node (ref "C33") (pin "1") (pinfunction "1_1") (pintype "passive"))
      (node (ref "U4") (pin "67") (pinfunction "VREF_67") (pintype "passive"))
    )
    (net (code "87") (name "Net-(X3-V_BUS)") (class "Default")
      (node (ref "L1") (pin "1") (pinfunction "1_1") (pintype "passive"))
      (node (ref "X3") (pin "1") (pinfunction "V_BUS_1") (pintype "passive"))
    )
    (net (code "88") (name "unconnected-(U1-PA4-Pad14)") (class "Default")
      (node (ref "U1") (pin "14") (pinfunction "PA4_14") (pintype "bidirectional"))
    )
    (net (code "89") (name "unconnected-(U1-PA5-Pad15)") (class "Default")
      (node (ref "U1") (pin "15") (pinfunction "PA5_15") (pintype "bidirectional"))
    )
    (net (code "90") (name "unconnected-(U1-PA6-Pad16)") (class "Default")
      (node (ref "U1") (pin "16") (pinfunction "PA6_16") (pintype "bidirectional"))
    )
    (net (code "91") (name "unconnected-(U1-PA7-Pad17)") (class "Default")
      (node (ref "U1") (pin "17") (pinfunction "PA7_17") (pintype "bidirectional"))
    )
    (net (code "92") (name "unconnected-(U1-PA8-Pad29)") (class "Default")
      (node (ref "U1") (pin "29") (pinfunction "PA8_29") (pintype "bidirectional"))
    )
    (net (code "93") (name "unconnected-(U1-PA15{slash}JTDI-Pad38)") (class "Default")
      (node (ref "U1") (pin "38") (pinfunction "PA15/JTDI_38") (pintype "bidirectional"))
    )
    (net (code "94") (name "unconnected-(U1-PB2{slash}BOOT1-Pad20)") (class "Default")
      (node (ref "U1") (pin "20") (pinfunction "PB2/BOOT1_20") (pintype "bidirectional"))
    )
    (net (code "95") (name "unconnected-(U1-PB4{slash}JNTRST-Pad40)") (class "Default")
      (node (ref "U1") (pin "40") (pinfunction "PB4/JNTRST_40") (pintype "bidirectional"))
    )
    (net (code "96") (name "unconnected-(U1-PB5-Pad41)") (class "Default")
      (node (ref "U1") (pin "41") (pinfunction "PB5_41") (pintype "bidirectional"))
    )
    (net (code "97") (name "unconnected-(U1-PB6-Pad42)") (class "Default")
      (node (ref "U1") (pin "42") (pinfunction "PB6_42") (pintype "bidirectional"))
    )
    (net (code "98") (name "unconnected-(U1-PB7-Pad43)") (class "Default")
      (node (ref "U1") (pin "43") (pinfunction "PB7_43") (pintype "bidirectional"))
    )
    (net (code "99") (name "unconnected-(U1-PB8-Pad45)") (class "Default")
      (node (ref "U1") (pin "45") (pinfunction "PB8_45") (pintype "bidirectional"))
    )
    (net (code "100") (name "unconnected-(U1-PB9-Pad46)") (class "Default")
      (node (ref "U1") (pin "46") (pinfunction "PB9_46") (pintype "bidirectional"))
    )
    (net (code "101") (name "unconnected-(U1-PB10-Pad21)") (class "Default")
      (node (ref "U1") (pin "21") (pinfunction "PB10_21") (pintype "bidirectional"))
    )
    (net (code "102") (name "unconnected-(U1-PB11-Pad22)") (class "Default")
      (node (ref "U1") (pin "22") (pinfunction "PB11_22") (pintype "bidirectional"))
    )
    (net (code "103") (name "unconnected-(U1-PB14-Pad27)") (class "Default")
      (node (ref "U1") (pin "27") (pinfunction "PB14_27") (pintype "bidirectional"))
    )
    (net (code "104") (name "unconnected-(U1-PC13-TAMPER-RTC-Pad2)") (class "Default")
      (node (ref "U1") (pin "2") (pinfunction "PC13-TAMPER-RTC_2") (pintype "bidirectional"))
    )
    (net (code "105") (name "unconnected-(U2A-REGIN-Pad7)") (class "Default")
      (node (ref "U2") (pin "7") (pinfunction "REGIN_7") (pintype "power_in"))
    )
    (net (code "106") (name "unconnected-(U2A-SUSPEND-Pad12)") (class "Default")
      (node (ref "U2") (pin "12") (pinfunction "SUSPEND_12") (pintype "output"))
    )
    (net (code "107") (name "unconnected-(U2A-~{CTS}-Pad23)") (class "Default")
      (node (ref "U2") (pin "23") (pinfunction "~{CTS}_23") (pintype "input"))
    )
    (net (code "108") (name "unconnected-(U2A-~{DCD}-Pad1)") (class "Default")
      (node (ref "U2") (pin "1") (pinfunction "~{DCD}_1") (pintype "input"))
    )
    (net (code "109") (name "unconnected-(U2A-~{DSR}-Pad27)") (class "Default")
      (node (ref "U2") (pin "27") (pinfunction "~{DSR}_27") (pintype "input"))
    )
    (net (code "110") (name "unconnected-(U2A-~{DTR}-Pad28)") (class "Default")
      (node (ref "U2") (pin "28") (pinfunction "~{DTR}_28") (pintype "output"))
    )
    (net (code "111") (name "unconnected-(U2A-~{RI}-Pad2)") (class "Default")
      (node (ref "U2") (pin "2") (pinfunction "~{RI}_2") (pintype "input"))
    )
    (net (code "112") (name "unconnected-(U2A-~{RST}-Pad9)") (class "Default")
      (node (ref "U2") (pin "9") (pinfunction "~{RST}_9") (pintype "bidirectional"))
    )
    (net (code "113") (name "unconnected-(U2A-~{RTS}-Pad24)") (class "Default")
      (node (ref "U2") (pin "24") (pinfunction "~{RTS}_24") (pintype "output"))
    )
    (net (code "114") (name "unconnected-(U2A-~{SUSPEND}-Pad11)") (class "Default")
      (node (ref "U2") (pin "11") (pinfunction "~{SUSPEND}_11") (pintype "output"))
    )
    (net (code "115") (name "unconnected-(U3-VREF-Pad5)") (class "Default")
      (node (ref "U3") (pin "5") (pinfunction "VREF_5") (pintype "output"))
    )
    (net (code "116") (name "unconnected-(U4-AUX0-Pad66)") (class "Default")
      (node (ref "U4") (pin "66") (pinfunction "AUX0_66") (pintype "passive"))
    )
    (net (code "117") (name "unconnected-(U4-AUX1-Pad65)") (class "Default")
      (node (ref "U4") (pin "65") (pinfunction "AUX1_65") (pintype "passive"))
    )
    (net (code "118") (name "unconnected-(U4-AUX2-Pad64)") (class "Default")
      (node (ref "U4") (pin "64") (pinfunction "AUX2_64") (pintype "passive"))
    )
    (net (code "119") (name "unconnected-(U4-AUX3-Pad63)") (class "Default")
      (node (ref "U4") (pin "63") (pinfunction "AUX3_63") (pintype "passive"))
    )
    (net (code "120") (name "unconnected-(U4-AUX4-Pad62)") (class "Default")
      (node (ref "U4") (pin "62") (pinfunction "AUX4_62") (pintype "passive"))
    )
    (net (code "121") (name "unconnected-(U4-AUX5-Pad61)") (class "Default")
      (node (ref "U4") (pin "61") (pinfunction "AUX5_61") (pintype "passive"))
    )
    (net (code "122") (name "unconnected-(U4-AUX6-Pad60)") (class "Default")
      (node (ref "U4") (pin "60") (pinfunction "AUX6_60") (pintype "passive"))
    )
    (net (code "123") (name "unconnected-(U4-AUX7-Pad59)") (class "Default")
      (node (ref "U4") (pin "59") (pinfunction "AUX7_59") (pintype "passive"))
    )
    (net (code "124") (name "unconnected-(U4-COMMH+-Pad55)") (class "Default")
      (node (ref "U4") (pin "55") (pinfunction "COMMH+_55") (pintype "passive"))
    )
    (net (code "125") (name "unconnected-(U4-COMMH--Pad54)") (class "Default")
      (node (ref "U4") (pin "54") (pinfunction "COMMH-_54") (pintype "passive"))
    )
    (net (code "126") (name "unconnected-(U4-COMML+-Pad52)") (class "Default")
      (node (ref "U4") (pin "52") (pinfunction "COMML+_52") (pintype "passive"))
    )
    (net (code "127") (name "unconnected-(U4-COMML--Pad53)") (class "Default")
      (node (ref "U4") (pin "53") (pinfunction "COMML-_53") (pintype "passive"))
    )
    (net (code "128") (name "unconnected-(U4-EQ1-Pad28)") (class "Default")
      (node (ref "U4") (pin "28") (pinfunction "EQ1_28") (pintype "passive"))
    )
    (net (code "129") (name "unconnected-(U4-EQ2-Pad26)") (class "Default")
      (node (ref "U4") (pin "26") (pinfunction "EQ2_26") (pintype "passive"))
    )
    (net (code "130") (name "unconnected-(U4-EQ3-Pad24)") (class "Default")
      (node (ref "U4") (pin "24") (pinfunction "EQ3_24") (pintype "passive"))
    )
    (net (code "131") (name "unconnected-(U4-EQ4-Pad22)") (class "Default")
      (node (ref "U4") (pin "22") (pinfunction "EQ4_22") (pintype "passive"))
    )
    (net (code "132") (name "unconnected-(U4-EQ5-Pad20)") (class "Default")
      (node (ref "U4") (pin "20") (pinfunction "EQ5_20") (pintype "passive"))
    )
    (net (code "133") (name "unconnected-(U4-EQ6-Pad18)") (class "Default")
      (node (ref "U4") (pin "18") (pinfunction "EQ6_18") (pintype "passive"))
    )
    (net (code "134") (name "unconnected-(U4-EQ7-Pad16)") (class "Default")
      (node (ref "U4") (pin "16") (pinfunction "EQ7_16") (pintype "passive"))
    )
    (net (code "135") (name "unconnected-(U4-EQ8-Pad14)") (class "Default")
      (node (ref "U4") (pin "14") (pinfunction "EQ8_14") (pintype "passive"))
    )
    (net (code "136") (name "unconnected-(U4-EQ9-Pad12)") (class "Default")
      (node (ref "U4") (pin "12") (pinfunction "EQ9_12") (pintype "passive"))
    )
    (net (code "137") (name "unconnected-(U4-EQ10-Pad10)") (class "Default")
      (node (ref "U4") (pin "10") (pinfunction "EQ10_10") (pintype "passive"))
    )
    (net (code "138") (name "unconnected-(U4-EQ11-Pad8)") (class "Default")
      (node (ref "U4") (pin "8") (pinfunction "EQ11_8") (pintype "passive"))
    )
    (net (code "139") (name "unconnected-(U4-EQ12-Pad6)") (class "Default")
      (node (ref "U4") (pin "6") (pinfunction "EQ12_6") (pintype "passive"))
    )
    (net (code "140") (name "unconnected-(U4-EQ13-Pad4)") (class "Default")
      (node (ref "U4") (pin "4") (pinfunction "EQ13_4") (pintype "passive"))
    )
    (net (code "141") (name "unconnected-(U4-EQ14-Pad2)") (class "Default")
      (node (ref "U4") (pin "2") (pinfunction "EQ14_2") (pintype "passive"))
    )
    (net (code "142") (name "unconnected-(U4-EQ15-Pad80)") (class "Default")
      (node (ref "U4") (pin "80") (pinfunction "EQ15_80") (pintype "passive"))
    )
    (net (code "143") (name "unconnected-(U4-EQ16-Pad78)") (class "Default")
      (node (ref "U4") (pin "78") (pinfunction "EQ16_78") (pintype "passive"))
    )
    (net (code "144") (name "unconnected-(U4-FAULH--Pad56)") (class "Default")
      (node (ref "U4") (pin "56") (pinfunction "FAULH-_56") (pintype "passive"))
    )
    (net (code "145") (name "unconnected-(U4-FAULTH+-Pad57)") (class "Default")
      (node (ref "U4") (pin "57") (pinfunction "FAULTH+_57") (pintype "passive"))
    )
    (net (code "146") (name "unconnected-(U4-FAULTL+-Pad50)") (class "Default")
      (node (ref "U4") (pin "50") (pinfunction "FAULTL+_50") (pintype "passive"))
    )
    (net (code "147") (name "unconnected-(U4-FAULTL--Pad51)") (class "Default")
      (node (ref "U4") (pin "51") (pinfunction "FAULTL-_51") (pintype "passive"))
    )
    (net (code "148") (name "unconnected-(U4-FAULT_N-Pad40)") (class "Default")
      (node (ref "U4") (pin "40") (pinfunction "FAULT_N_40") (pintype "passive"))
    )
    (net (code "149") (name "unconnected-(U4-GPIO0-Pad47)") (class "Default")
      (node (ref "U4") (pin "47") (pinfunction "GPIO0_47") (pintype "passive"))
    )
    (net (code "150") (name "unconnected-(U4-GPIO1-Pad46)") (class "Default")
      (node (ref "U4") (pin "46") (pinfunction "GPIO1_46") (pintype "passive"))
    )
    (net (code "151") (name "unconnected-(U4-GPIO2-Pad45)") (class "Default")
      (node (ref "U4") (pin "45") (pinfunction "GPIO2_45") (pintype "passive"))
    )
    (net (code "152") (name "unconnected-(U4-GPIO3-Pad44)") (class "Default")
      (node (ref "U4") (pin "44") (pinfunction "GPIO3_44") (pintype "passive"))
    )
    (net (code "153") (name "unconnected-(U4-GPIO4-Pad43)") (class "Default")
      (node (ref "U4") (pin "43") (pinfunction "GPIO4_43") (pintype "passive"))
    )
    (net (code "154") (name "unconnected-(U4-GPIO5-Pad42)") (class "Default")
      (node (ref "U4") (pin "42") (pinfunction "GPIO5_42") (pintype "passive"))
    )
    (net (code "155") (name "unconnected-(U4-NC1-Pad36)") (class "Default")
      (node (ref "U4") (pin "36") (pinfunction "NC1_36") (pintype "passive"))
    )
    (net (code "156") (name "unconnected-(U4-NC2-Pad75)") (class "Default")
      (node (ref "U4") (pin "75") (pinfunction "NC2_75") (pintype "passive"))
    )
    (net (code "157") (name "unconnected-(X3-ID-Pad4)") (class "Default")
      (node (ref "X3") (pin "4") (pinfunction "ID_4") (pintype "passive"))
    )
    (net (code "158") (name "unconnected-(X7-Pad3)") (class "Default")
      (node (ref "X7") (pin "3") (pinfunction "3_3") (pintype "passive"))
    )
    (net (code "159") (name "unconnected-(X7-Pad5)") (class "Default")
      (node (ref "X7") (pin "5") (pinfunction "5_5") (pintype "passive"))
    )
    (net (code "160") (name "unconnected-(X7-Pad7)") (class "Default")
      (node (ref "X7") (pin "7") (pinfunction "7_7") (pintype "passive"))
    )
    (net (code "161") (name "unconnected-(X9-Pad3)") (class "Default")
      (node (ref "X9") (pin "3") (pinfunction "3_3") (pintype "passive"))
    )
    (net (code "162") (name "unconnected-(X9-Pad5)") (class "Default")
      (node (ref "X9") (pin "5") (pinfunction "5_5") (pintype "passive"))
    )
    (net (code "163") (name "unconnected-(X9-Pad7)") (class "Default")
      (node (ref "X9") (pin "7") (pinfunction "7_7") (pintype "passive"))
    )
  )
)
